# SallenKey2Orden.net
KiCad netlist of a schematic drawn in EasyEDA
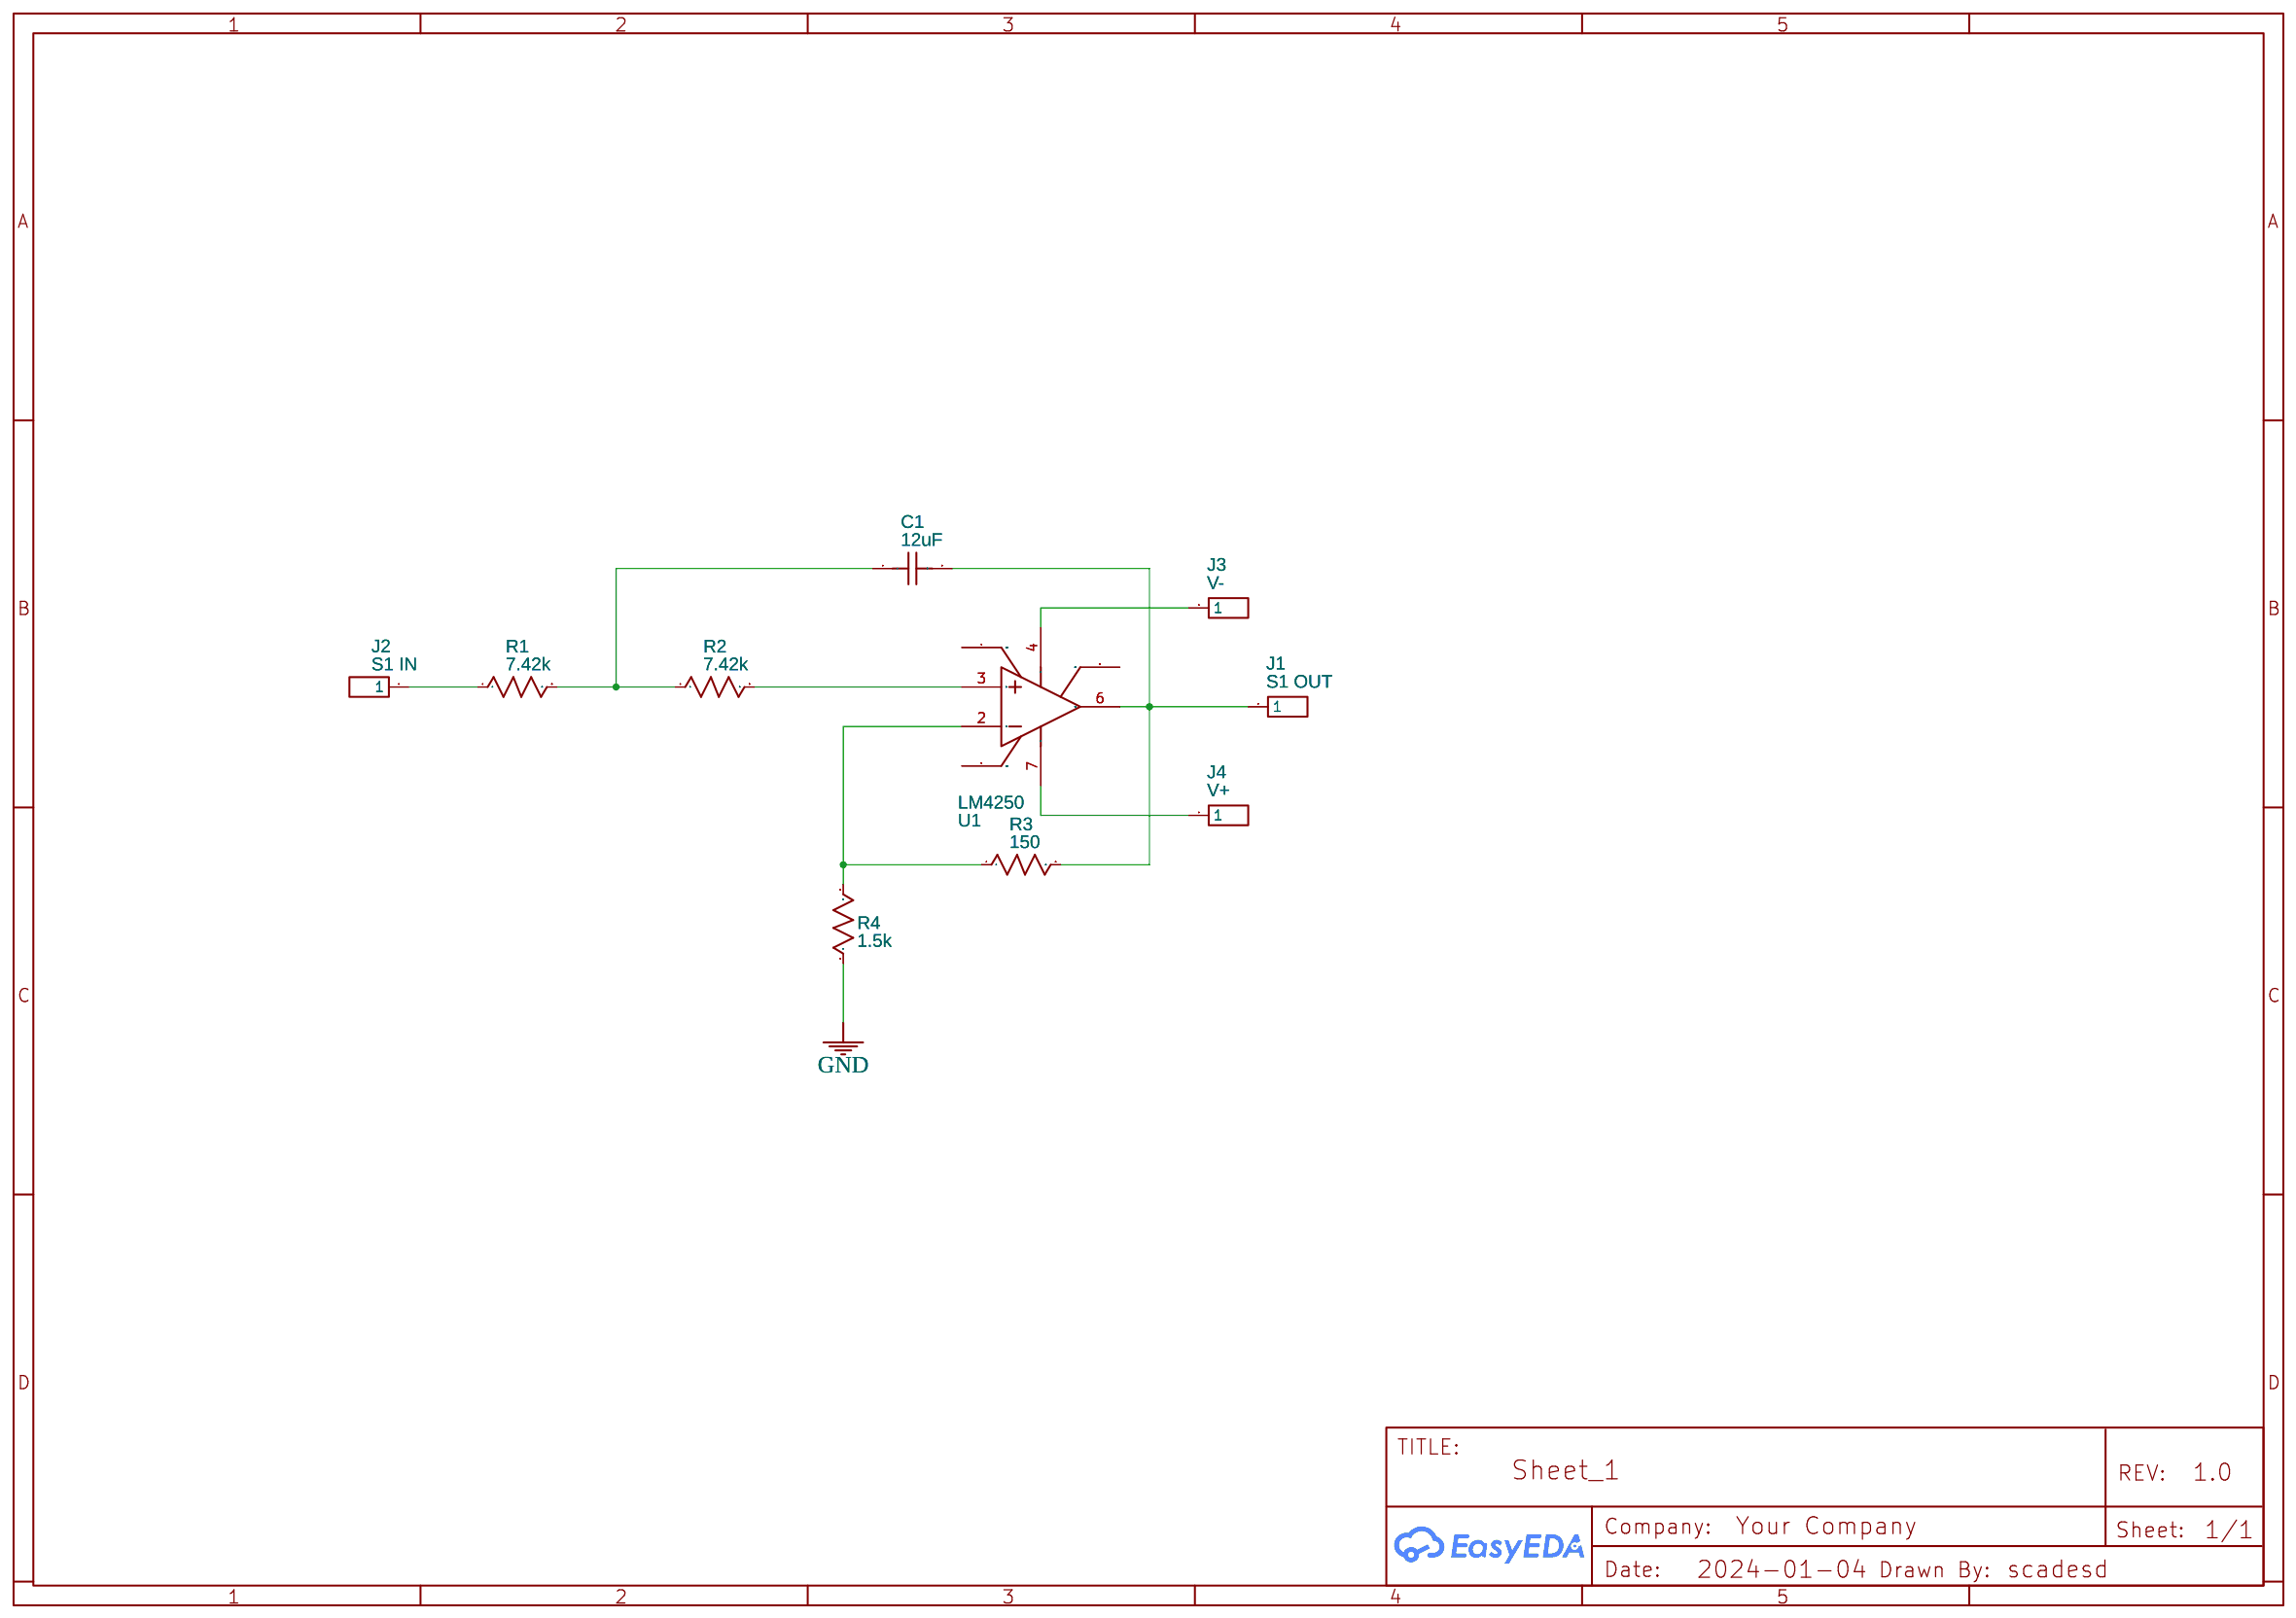
[diagram p0: schematic sheet]

(export (version "E")
  (design (tool "Eeschema 10.0.6"))
  (components
    (comp (ref "C1") (value "12uF") (libsource (lib "") (part "C_0603_US")))
    (comp (ref "J1") (value "S1 OUT") (libsource (lib "") (part "HDR-M-2.54_1x1")))
    (comp (ref "J2") (value "S1 IN") (libsource (lib "") (part "HDR-M-2.54_1x1_1")))
    (comp (ref "J3") (value "V-") (libsource (lib "") (part "HDR-M-2.54_1x1")))
    (comp (ref "J4") (value "V+") (libsource (lib "") (part "HDR-M-2.54_1x1")))
    (comp (ref "R1") (value "7.42k") (libsource (lib "") (part "R_0603_US")))
    (comp (ref "R2") (value "7.42k") (libsource (lib "") (part "R_0603_US")))
    (comp (ref "R3") (value "150") (libsource (lib "") (part "R_0603_US")))
    (comp (ref "R4") (value "1.5k") (libsource (lib "") (part "R_0603_US_1")))
    (comp (ref "U1")
      (value "LM4250")
      (fields (field (name "Manufacturer Part") "LM4250CN/NOPB") (field (name "Manufacturer") "TI(德州仪器)"))
      (libsource (lib "") (part "LM4250CN/NOPB"))
    )
  )
  (nets
    (net (code "1") (name "GND") (class "Default")
      (node (ref "R4") (pin "1") (pinfunction "1_1") (pintype "unspecified"))
    )
    (net (code "2") (name "Net-(C1-Pad1)") (class "Default")
      (node (ref "C1") (pin "1") (pinfunction "1_1") (pintype "unspecified"))
      (node (ref "R1") (pin "2") (pinfunction "2_2") (pintype "unspecified"))
      (node (ref "R2") (pin "1") (pinfunction "1_1") (pintype "unspecified"))
    )
    (net (code "3") (name "Net-(J2-Pad1)") (class "Default")
      (node (ref "J2") (pin "1") (pinfunction "1_1") (pintype "input"))
      (node (ref "R1") (pin "1") (pinfunction "1_1") (pintype "unspecified"))
    )
    (net (code "4") (name "Net-(U1-IN+)") (class "Default")
      (node (ref "R2") (pin "2") (pinfunction "2_2") (pintype "unspecified"))
      (node (ref "U1") (pin "3") (pinfunction "IN+_3") (pintype "unspecified"))
    )
    (net (code "5") (name "Net-(U1-IN-)") (class "Default")
      (node (ref "R3") (pin "1") (pinfunction "1_1") (pintype "unspecified"))
      (node (ref "R4") (pin "2") (pinfunction "2_2") (pintype "unspecified"))
      (node (ref "U1") (pin "2") (pinfunction "IN-_2") (pintype "unspecified"))
    )
    (net (code "6") (name "Net-(U1-OUT)") (class "Default")
      (node (ref "C1") (pin "2") (pinfunction "2_2") (pintype "unspecified"))
      (node (ref "J1") (pin "1") (pinfunction "1_1") (pintype "input"))
      (node (ref "R3") (pin "2") (pinfunction "2_2") (pintype "unspecified"))
      (node (ref "U1") (pin "6") (pinfunction "OUT_6") (pintype "output"))
    )
    (net (code "7") (name "Net-(U1-V+)") (class "Default")
      (node (ref "J4") (pin "1") (pinfunction "1_1") (pintype "input"))
      (node (ref "U1") (pin "7") (pinfunction "V+_7") (pintype "passive"))
    )
    (net (code "8") (name "Net-(U1-V-)") (class "Default")
      (node (ref "J3") (pin "1") (pinfunction "1_1") (pintype "input"))
      (node (ref "U1") (pin "4") (pinfunction "V-_4") (pintype "passive"))
    )
    (net (code "9") (name "unconnected-(U1-I_SET-Pad8)") (class "Default")
      (node (ref "U1") (pin "8") (pinfunction "I_SET_8") (pintype "unspecified"))
    )
    (net (code "10") (name "unconnected-(U1-OFS_NULL-Pad1)") (class "Default")
      (node (ref "U1") (pin "1") (pinfunction "OFS_NULL_1") (pintype "unspecified"))
    )
    (net (code "11") (name "unconnected-(U1-OFS_NULL-Pad5)") (class "Default")
      (node (ref "U1") (pin "5") (pinfunction "OFS_NULL_5") (pintype "unspecified"))
    )
  )
)
